# Rectifier.net
KiCad netlist of a schematic drawn in EAGLE
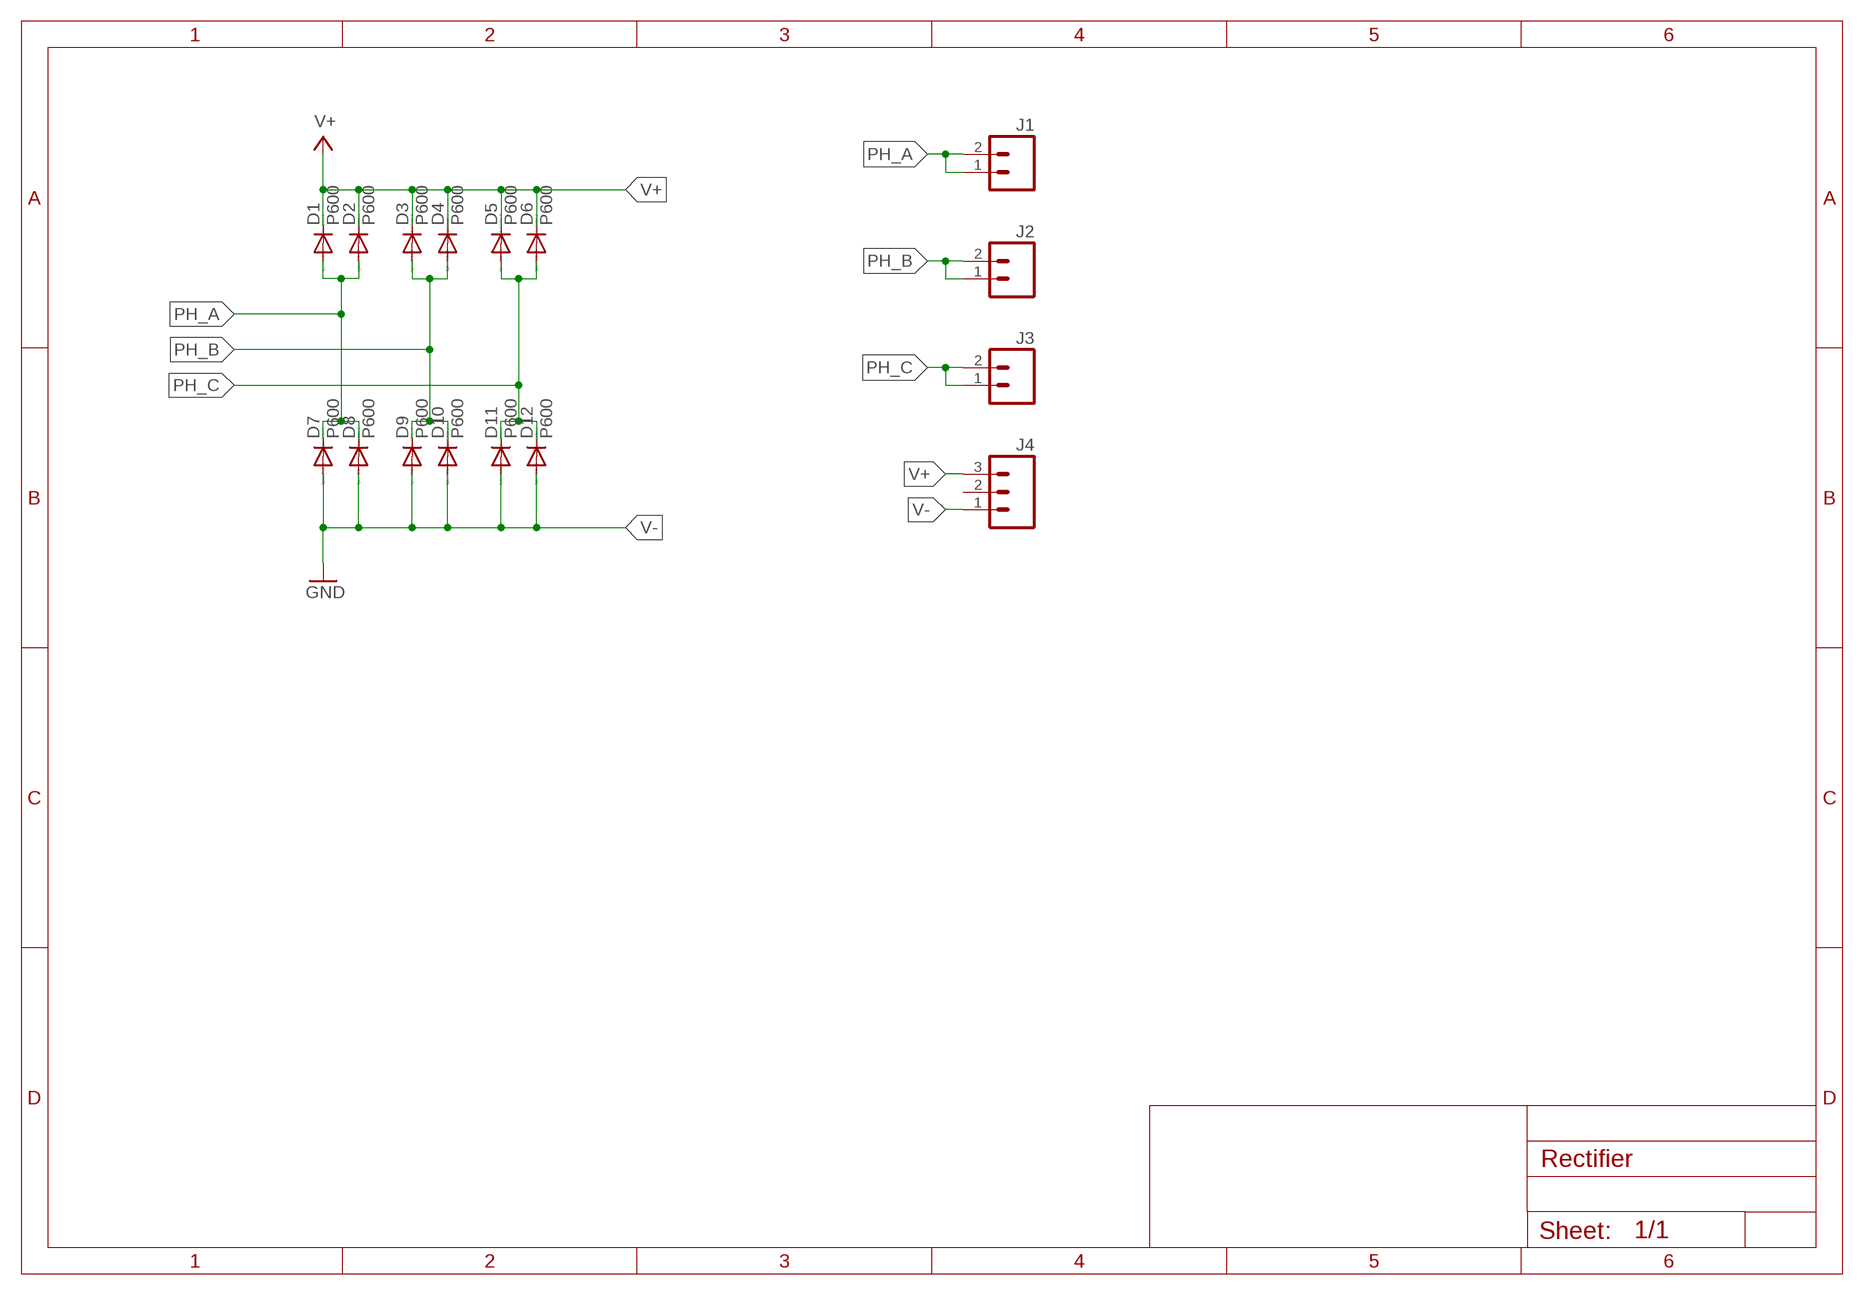
[diagram p0: schematic, sheet 1]

(export (version "E")
  (design (tool "Eeschema 10.0.6"))
  (components
    (comp (ref "D1")
      (value "P600")
      (footprint "eagle-import:P6-15")
      (libsource (lib "eagle-import") (part "P600"))
    )
    (comp (ref "D2")
      (value "P600")
      (footprint "eagle-import:P6-15")
      (libsource (lib "eagle-import") (part "P600"))
    )
    (comp (ref "D3")
      (value "P600")
      (footprint "eagle-import:P6-15")
      (libsource (lib "eagle-import") (part "P600"))
    )
    (comp (ref "D4")
      (value "P600")
      (footprint "eagle-import:P6-15")
      (libsource (lib "eagle-import") (part "P600"))
    )
    (comp (ref "D5")
      (value "P600")
      (footprint "eagle-import:P6-15")
      (libsource (lib "eagle-import") (part "P600"))
    )
    (comp (ref "D6")
      (value "P600")
      (footprint "eagle-import:P6-15")
      (libsource (lib "eagle-import") (part "P600"))
    )
    (comp (ref "D7")
      (value "P600")
      (footprint "eagle-import:P6-15")
      (libsource (lib "eagle-import") (part "P600"))
    )
    (comp (ref "D8")
      (value "P600")
      (footprint "eagle-import:P6-15")
      (libsource (lib "eagle-import") (part "P600"))
    )
    (comp (ref "D9")
      (value "P600")
      (footprint "eagle-import:P6-15")
      (libsource (lib "eagle-import") (part "P600"))
    )
    (comp (ref "D10")
      (value "P600")
      (footprint "eagle-import:P6-15")
      (libsource (lib "eagle-import") (part "P600"))
    )
    (comp (ref "D11")
      (value "P600")
      (footprint "eagle-import:P6-15")
      (libsource (lib "eagle-import") (part "P600"))
    )
    (comp (ref "D12")
      (value "P600")
      (footprint "eagle-import:P6-15")
      (libsource (lib "eagle-import") (part "P600"))
    )
    (comp (ref "J1")
      (value "M025MM")
      (footprint "eagle-import:SCREWTERMINAL-5MM-2")
      (libsource (lib "eagle-import") (part "M025MM"))
    )
    (comp (ref "J2")
      (value "M025MM")
      (footprint "eagle-import:SCREWTERMINAL-5MM-2")
      (libsource (lib "eagle-import") (part "M025MM"))
    )
    (comp (ref "J3")
      (value "M025MM")
      (footprint "eagle-import:SCREWTERMINAL-5MM-2")
      (libsource (lib "eagle-import") (part "M025MM"))
    )
    (comp (ref "J4")
      (value "M03-SCREW-5MM")
      (footprint "eagle-import:SCREWTERMINAL-5MM-3")
      (libsource (lib "eagle-import") (part "M03-SCREW-5MM"))
    )
  )
  (nets
    (net (code "1") (name "PH_A") (class "Default")
      (node (ref "D1") (pin "A") (pinfunction "A_A") (pintype "passive"))
      (node (ref "D2") (pin "A") (pinfunction "A_A") (pintype "passive"))
      (node (ref "D7") (pin "C") (pinfunction "C_C") (pintype "passive"))
      (node (ref "D8") (pin "C") (pinfunction "C_C") (pintype "passive"))
      (node (ref "J1") (pin "1") (pinfunction "1_1") (pintype "passive"))
      (node (ref "J1") (pin "2") (pinfunction "2_2") (pintype "passive"))
    )
    (net (code "2") (name "PH_B") (class "Default")
      (node (ref "D10") (pin "C") (pinfunction "C_C") (pintype "passive"))
      (node (ref "D3") (pin "A") (pinfunction "A_A") (pintype "passive"))
      (node (ref "D4") (pin "A") (pinfunction "A_A") (pintype "passive"))
      (node (ref "D9") (pin "C") (pinfunction "C_C") (pintype "passive"))
      (node (ref "J2") (pin "1") (pinfunction "1_1") (pintype "passive"))
      (node (ref "J2") (pin "2") (pinfunction "2_2") (pintype "passive"))
    )
    (net (code "3") (name "PH_C") (class "Default")
      (node (ref "D11") (pin "C") (pinfunction "C_C") (pintype "passive"))
      (node (ref "D12") (pin "C") (pinfunction "C_C") (pintype "passive"))
      (node (ref "D5") (pin "A") (pinfunction "A_A") (pintype "passive"))
      (node (ref "D6") (pin "A") (pinfunction "A_A") (pintype "passive"))
      (node (ref "J3") (pin "1") (pinfunction "1_1") (pintype "passive"))
      (node (ref "J3") (pin "2") (pinfunction "2_2") (pintype "passive"))
    )
    (net (code "4") (name "V+") (class "Default")
      (node (ref "D1") (pin "C") (pinfunction "C_C") (pintype "passive"))
      (node (ref "D2") (pin "C") (pinfunction "C_C") (pintype "passive"))
      (node (ref "D3") (pin "C") (pinfunction "C_C") (pintype "passive"))
      (node (ref "D4") (pin "C") (pinfunction "C_C") (pintype "passive"))
      (node (ref "D5") (pin "C") (pinfunction "C_C") (pintype "passive"))
      (node (ref "D6") (pin "C") (pinfunction "C_C") (pintype "passive"))
      (node (ref "J4") (pin "3") (pinfunction "3_3") (pintype "passive"))
    )
    (net (code "5") (name "V-") (class "Default")
      (node (ref "D10") (pin "A") (pinfunction "A_A") (pintype "passive"))
      (node (ref "D11") (pin "A") (pinfunction "A_A") (pintype "passive"))
      (node (ref "D12") (pin "A") (pinfunction "A_A") (pintype "passive"))
      (node (ref "D7") (pin "A") (pinfunction "A_A") (pintype "passive"))
      (node (ref "D8") (pin "A") (pinfunction "A_A") (pintype "passive"))
      (node (ref "D9") (pin "A") (pinfunction "A_A") (pintype "passive"))
      (node (ref "J4") (pin "1") (pinfunction "1_1") (pintype "passive"))
    )
    (net (code "6") (name "unconnected-(J4-Pad2)") (class "Default")
      (node (ref "J4") (pin "2") (pinfunction "2_2") (pintype "passive"))
    )
  )
)
